# untitled.net
KiCad netlist of a schematic drawn in EAGLE
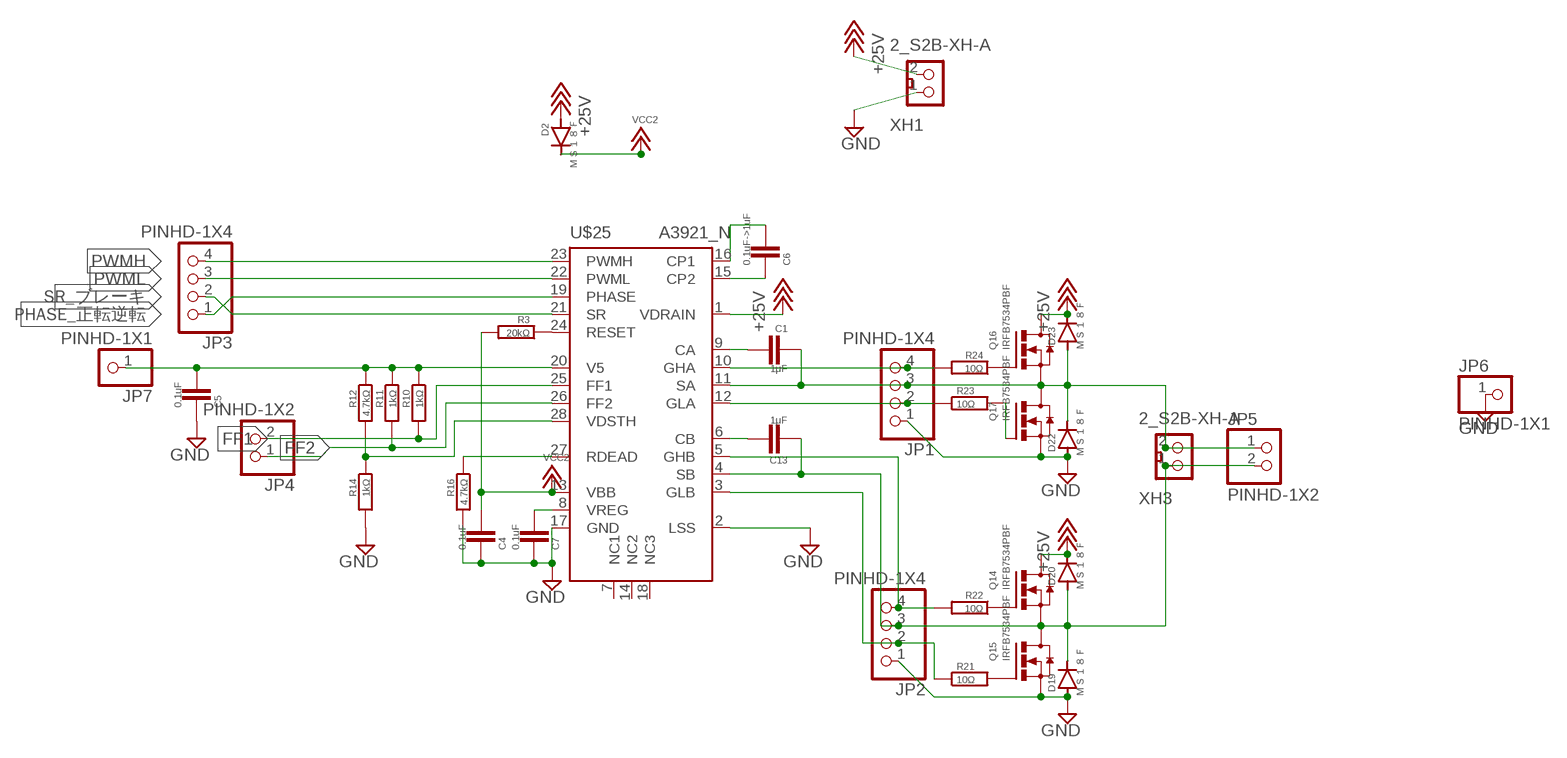
[diagram p0: schematic, sheet 1]

(export (version "E")
  (design (tool "Eeschema 10.0.6"))
  (components
    (comp (ref "C1")
      (value "1μF")
      (footprint "eagle-import:2012")
      (libsource (lib "eagle-import") (part "CAPACITOR{gt}{gt}2012"))
    )
    (comp (ref "C4")
      (value "0.1uF")
      (footprint "eagle-import:2012")
      (libsource (lib "eagle-import") (part "CAPACITOR{gt}{gt}2012"))
    )
    (comp (ref "C5")
      (value "0.1uF")
      (footprint "eagle-import:2012")
      (libsource (lib "eagle-import") (part "CAPACITOR{gt}{gt}2012"))
    )
    (comp (ref "C6")
      (value "0.1uF->1uF")
      (footprint "eagle-import:2012")
      (libsource (lib "eagle-import") (part "CAPACITOR{gt}{gt}2012"))
    )
    (comp (ref "C7")
      (value "0.1uF")
      (footprint "eagle-import:2012")
      (libsource (lib "eagle-import") (part "CAPACITOR{gt}{gt}2012"))
    )
    (comp (ref "C13")
      (value "1μF")
      (footprint "eagle-import:2012")
      (libsource (lib "eagle-import") (part "CAPACITOR{gt}{gt}2012"))
    )
    (comp (ref "D2")
      (value "ＭＳ１８Ｆ")
      (footprint "eagle-import:MS18F")
      (libsource (lib "eagle-import") (part "DIODE{gt}{gt}MS18F"))
    )
    (comp (ref "D19")
      (value "ＭＳ１８Ｆ")
      (footprint "eagle-import:MS18F")
      (libsource (lib "eagle-import") (part "DIODE{gt}{gt}MS18F"))
    )
    (comp (ref "D20")
      (value "ＭＳ１８Ｆ")
      (footprint "eagle-import:MS18F")
      (libsource (lib "eagle-import") (part "DIODE{gt}{gt}MS18F"))
    )
    (comp (ref "D22")
      (value "ＭＳ１８Ｆ")
      (footprint "eagle-import:MS18F")
      (libsource (lib "eagle-import") (part "DIODE{gt}{gt}MS18F"))
    )
    (comp (ref "D23")
      (value "ＭＳ１８Ｆ")
      (footprint "eagle-import:MS18F")
      (libsource (lib "eagle-import") (part "DIODE{gt}{gt}MS18F"))
    )
    (comp (ref "JP1")
      (value "PINHD-1X4")
      (footprint "eagle-import:1X04")
      (libsource (lib "eagle-import") (part "PINHD-1X4"))
    )
    (comp (ref "JP2")
      (value "PINHD-1X4")
      (footprint "eagle-import:1X04")
      (libsource (lib "eagle-import") (part "PINHD-1X4"))
    )
    (comp (ref "JP3")
      (value "PINHD-1X4")
      (footprint "eagle-import:1X04")
      (libsource (lib "eagle-import") (part "PINHD-1X4"))
    )
    (comp (ref "JP4")
      (value "PINHD-1X2")
      (footprint "eagle-import:1X02")
      (libsource (lib "eagle-import") (part "PINHD-1X2"))
    )
    (comp (ref "JP5")
      (value "PINHD-1X2")
      (footprint "eagle-import:1X02")
      (libsource (lib "eagle-import") (part "PINHD-1X2"))
    )
    (comp (ref "JP6")
      (value "PINHD-1X1")
      (footprint "eagle-import:1X01")
      (libsource (lib "eagle-import") (part "PINHD-1X1"))
    )
    (comp (ref "JP7")
      (value "PINHD-1X1")
      (footprint "eagle-import:1X01")
      (libsource (lib "eagle-import") (part "PINHD-1X1"))
    )
    (comp (ref "Q14")
      (value "IRFB7534PBF")
      (footprint "eagle-import:TO252")
      (libsource (lib "eagle-import") (part "MOSFET_N{gt}{gt}TO252"))
    )
    (comp (ref "Q15")
      (value "IRFB7534PBF")
      (footprint "eagle-import:TO252")
      (libsource (lib "eagle-import") (part "MOSFET_N{gt}{gt}TO252"))
    )
    (comp (ref "Q16")
      (value "IRFB7534PBF")
      (footprint "eagle-import:TO252")
      (libsource (lib "eagle-import") (part "MOSFET_N{gt}{gt}TO252"))
    )
    (comp (ref "Q17")
      (value "IRFB7534PBF")
      (footprint "eagle-import:TO252")
      (libsource (lib "eagle-import") (part "MOSFET_N{gt}{gt}TO252"))
    )
    (comp (ref "R3")
      (value "20kΩ")
      (footprint "eagle-import:2012")
      (libsource (lib "eagle-import") (part "REGISTER{gt}{gt}2012"))
    )
    (comp (ref "R10")
      (value "1kΩ")
      (footprint "eagle-import:2012")
      (libsource (lib "eagle-import") (part "REGISTER{gt}{gt}2012"))
    )
    (comp (ref "R11")
      (value "1kΩ")
      (footprint "eagle-import:2012")
      (libsource (lib "eagle-import") (part "REGISTER{gt}{gt}2012"))
    )
    (comp (ref "R12")
      (value "4.7kΩ")
      (footprint "eagle-import:2012")
      (libsource (lib "eagle-import") (part "REGISTER{gt}{gt}2012"))
    )
    (comp (ref "R14")
      (value "1kΩ")
      (footprint "eagle-import:2012")
      (libsource (lib "eagle-import") (part "REGISTER{gt}{gt}2012"))
    )
    (comp (ref "R16")
      (value "4.7kΩ")
      (footprint "eagle-import:2012")
      (libsource (lib "eagle-import") (part "REGISTER{gt}{gt}2012"))
    )
    (comp (ref "R21")
      (value "10Ω")
      (footprint "eagle-import:2012")
      (libsource (lib "eagle-import") (part "REGISTER{gt}{gt}2012"))
    )
    (comp (ref "R22")
      (value "10Ω")
      (footprint "eagle-import:2012")
      (libsource (lib "eagle-import") (part "REGISTER{gt}{gt}2012"))
    )
    (comp (ref "R23")
      (value "10Ω")
      (footprint "eagle-import:2012")
      (libsource (lib "eagle-import") (part "REGISTER{gt}{gt}2012"))
    )
    (comp (ref "R24")
      (value "10Ω")
      (footprint "eagle-import:2012")
      (libsource (lib "eagle-import") (part "REGISTER{gt}{gt}2012"))
    )
    (comp (ref "U$25")
      (value "A3921_N")
      (footprint "eagle-import:TSSOP28_N")
      (libsource (lib "eagle-import") (part "A3921_N"))
    )
    (comp (ref "XH1")
      (value "2_S2B-XH-A")
      (footprint "eagle-import:S2B-XH-A")
      (libsource (lib "eagle-import") (part "2_S2B-XH-A"))
    )
    (comp (ref "XH3")
      (value "2_S2B-XH-A")
      (footprint "eagle-import:S2B-XH-A")
      (libsource (lib "eagle-import") (part "2_S2B-XH-A"))
    )
  )
  (nets
    (net (code "1") (name "+25V") (class "Default")
      (node (ref "D2") (pin "P$1") (pinfunction "A_P$1") (pintype "passive"))
      (node (ref "D20") (pin "P$2") (pinfunction "C_P$2") (pintype "passive"))
      (node (ref "D23") (pin "P$2") (pinfunction "C_P$2") (pintype "passive"))
      (node (ref "Q14") (pin "3") (pinfunction "D_3") (pintype "passive"))
      (node (ref "Q16") (pin "3") (pinfunction "D_3") (pintype "passive"))
      (node (ref "U$25") (pin "1") (pinfunction "VDRAIN_1") (pintype "power_in"))
      (node (ref "XH1") (pin "2") (pinfunction "2_2") (pintype "passive"))
    )
    (net (code "2") (name "FF1") (class "Default")
      (node (ref "JP4") (pin "2") (pinfunction "2_2") (pintype "passive"))
      (node (ref "R10") (pin "2") (pinfunction "2_2") (pintype "passive"))
      (node (ref "U$25") (pin "25") (pinfunction "FF1_25") (pintype "output"))
    )
    (net (code "3") (name "FF2") (class "Default")
      (node (ref "JP4") (pin "1") (pinfunction "1_1") (pintype "passive"))
      (node (ref "R11") (pin "2") (pinfunction "2_2") (pintype "passive"))
      (node (ref "U$25") (pin "26") (pinfunction "FF2_26") (pintype "output"))
    )
    (net (code "4") (name "GND") (class "Default")
      (node (ref "C4") (pin "2") (pinfunction "2_2") (pintype "passive"))
      (node (ref "C5") (pin "2") (pinfunction "2_2") (pintype "passive"))
      (node (ref "C7") (pin "2") (pinfunction "2_2") (pintype "passive"))
      (node (ref "D19") (pin "P$1") (pinfunction "A_P$1") (pintype "passive"))
      (node (ref "D22") (pin "P$1") (pinfunction "A_P$1") (pintype "passive"))
      (node (ref "JP1") (pin "1") (pinfunction "1_1") (pintype "passive"))
      (node (ref "JP2") (pin "1") (pinfunction "1_1") (pintype "passive"))
      (node (ref "JP6") (pin "1") (pinfunction "1_1") (pintype "passive"))
      (node (ref "Q15") (pin "2") (pinfunction "S_2") (pintype "passive"))
      (node (ref "Q17") (pin "2") (pinfunction "S_2") (pintype "passive"))
      (node (ref "R14") (pin "2") (pinfunction "2_2") (pintype "passive"))
      (node (ref "R16") (pin "2") (pinfunction "2_2") (pintype "passive"))
      (node (ref "U$25") (pin "17") (pinfunction "GND_17") (pintype "power_in"))
      (node (ref "U$25") (pin "2") (pinfunction "LSS_2") (pintype "passive"))
      (node (ref "XH1") (pin "1") (pinfunction "1_1") (pintype "passive"))
    )
    (net (code "5") (name "Net-(D19-C)") (class "Default")
      (node (ref "C13") (pin "2") (pinfunction "2_2") (pintype "passive"))
      (node (ref "D19") (pin "P$2") (pinfunction "C_P$2") (pintype "passive"))
      (node (ref "D20") (pin "P$1") (pinfunction "A_P$1") (pintype "passive"))
      (node (ref "JP2") (pin "3") (pinfunction "3_3") (pintype "passive"))
      (node (ref "JP5") (pin "2") (pinfunction "2_2") (pintype "passive"))
      (node (ref "Q14") (pin "2") (pinfunction "S_2") (pintype "passive"))
      (node (ref "Q15") (pin "3") (pinfunction "D_3") (pintype "passive"))
      (node (ref "U$25") (pin "4") (pinfunction "SB_4") (pintype "output"))
      (node (ref "XH3") (pin "1") (pinfunction "1_1") (pintype "passive"))
    )
    (net (code "6") (name "Net-(D22-C)") (class "Default")
      (node (ref "C1") (pin "2") (pinfunction "2_2") (pintype "passive"))
      (node (ref "D22") (pin "P$2") (pinfunction "C_P$2") (pintype "passive"))
      (node (ref "D23") (pin "P$1") (pinfunction "A_P$1") (pintype "passive"))
      (node (ref "JP1") (pin "3") (pinfunction "3_3") (pintype "passive"))
      (node (ref "JP5") (pin "1") (pinfunction "1_1") (pintype "passive"))
      (node (ref "Q16") (pin "2") (pinfunction "S_2") (pintype "passive"))
      (node (ref "Q17") (pin "3") (pinfunction "D_3") (pintype "passive"))
      (node (ref "U$25") (pin "11") (pinfunction "SA_11") (pintype "output"))
      (node (ref "XH3") (pin "2") (pinfunction "2_2") (pintype "passive"))
    )
    (net (code "7") (name "Net-(Q14-G)") (class "Default")
      (node (ref "Q14") (pin "1") (pinfunction "G_1") (pintype "passive"))
      (node (ref "R22") (pin "1") (pinfunction "1_1") (pintype "passive"))
    )
    (net (code "8") (name "Net-(Q15-G)") (class "Default")
      (node (ref "Q15") (pin "1") (pinfunction "G_1") (pintype "passive"))
      (node (ref "R21") (pin "2") (pinfunction "2_2") (pintype "passive"))
    )
    (net (code "9") (name "Net-(Q16-G)") (class "Default")
      (node (ref "Q16") (pin "1") (pinfunction "G_1") (pintype "passive"))
      (node (ref "R24") (pin "1") (pinfunction "1_1") (pintype "passive"))
    )
    (net (code "10") (name "Net-(Q17-G)") (class "Default")
      (node (ref "Q17") (pin "1") (pinfunction "G_1") (pintype "passive"))
      (node (ref "R23") (pin "2") (pinfunction "2_2") (pintype "passive"))
    )
    (net (code "11") (name "Net-(U$25-CA)") (class "Default")
      (node (ref "C1") (pin "1") (pinfunction "1_1") (pintype "passive"))
      (node (ref "U$25") (pin "9") (pinfunction "CA_9") (pintype "input"))
    )
    (net (code "12") (name "Net-(U$25-CB)") (class "Default")
      (node (ref "C13") (pin "1") (pinfunction "1_1") (pintype "passive"))
      (node (ref "U$25") (pin "6") (pinfunction "CB_6") (pintype "input"))
    )
    (net (code "13") (name "Net-(U$25-CP1)") (class "Default")
      (node (ref "C6") (pin "1") (pinfunction "1_1") (pintype "passive"))
      (node (ref "U$25") (pin "16") (pinfunction "CP1_16") (pintype "passive"))
    )
    (net (code "14") (name "Net-(U$25-CP2)") (class "Default")
      (node (ref "C6") (pin "2") (pinfunction "2_2") (pintype "passive"))
      (node (ref "U$25") (pin "15") (pinfunction "CP2_15") (pintype "passive"))
    )
    (net (code "15") (name "Net-(U$25-GHA)") (class "Default")
      (node (ref "JP1") (pin "4") (pinfunction "4_4") (pintype "passive"))
      (node (ref "R24") (pin "2") (pinfunction "2_2") (pintype "passive"))
      (node (ref "U$25") (pin "10") (pinfunction "GHA_10") (pintype "output"))
    )
    (net (code "16") (name "Net-(U$25-GHB)") (class "Default")
      (node (ref "JP2") (pin "4") (pinfunction "4_4") (pintype "passive"))
      (node (ref "R22") (pin "2") (pinfunction "2_2") (pintype "passive"))
      (node (ref "U$25") (pin "5") (pinfunction "GHB_5") (pintype "output"))
    )
    (net (code "17") (name "Net-(U$25-GLA)") (class "Default")
      (node (ref "JP1") (pin "2") (pinfunction "2_2") (pintype "passive"))
      (node (ref "R23") (pin "1") (pinfunction "1_1") (pintype "passive"))
      (node (ref "U$25") (pin "12") (pinfunction "GLA_12") (pintype "output"))
    )
    (net (code "18") (name "Net-(U$25-GLB)") (class "Default")
      (node (ref "JP2") (pin "2") (pinfunction "2_2") (pintype "passive"))
      (node (ref "R21") (pin "1") (pinfunction "1_1") (pintype "passive"))
      (node (ref "U$25") (pin "3") (pinfunction "GLB_3") (pintype "output"))
    )
    (net (code "19") (name "Net-(U$25-RDEAD)") (class "Default")
      (node (ref "R16") (pin "1") (pinfunction "1_1") (pintype "passive"))
      (node (ref "U$25") (pin "27") (pinfunction "RDEAD_27") (pintype "input"))
    )
    (net (code "20") (name "Net-(U$25-RESET)") (class "Default")
      (node (ref "R3") (pin "1") (pinfunction "1_1") (pintype "passive"))
      (node (ref "U$25") (pin "24") (pinfunction "RESET_24") (pintype "input"))
    )
    (net (code "21") (name "Net-(U$25-V5)") (class "Default")
      (node (ref "C5") (pin "1") (pinfunction "1_1") (pintype "passive"))
      (node (ref "JP7") (pin "1") (pinfunction "1_1") (pintype "passive"))
      (node (ref "R10") (pin "1") (pinfunction "1_1") (pintype "passive"))
      (node (ref "R11") (pin "1") (pinfunction "1_1") (pintype "passive"))
      (node (ref "R12") (pin "1") (pinfunction "1_1") (pintype "passive"))
      (node (ref "U$25") (pin "20") (pinfunction "V5_20") (pintype "power_in"))
    )
    (net (code "22") (name "Net-(U$25-VDSTH)") (class "Default")
      (node (ref "R12") (pin "2") (pinfunction "2_2") (pintype "passive"))
      (node (ref "R14") (pin "1") (pinfunction "1_1") (pintype "passive"))
      (node (ref "U$25") (pin "28") (pinfunction "VDSTH_28") (pintype "input"))
    )
    (net (code "23") (name "Net-(U$25-VREG)") (class "Default")
      (node (ref "C7") (pin "1") (pinfunction "1_1") (pintype "passive"))
      (node (ref "U$25") (pin "8") (pinfunction "VREG_8") (pintype "power_in"))
    )
    (net (code "24") (name "PHASE_正転逆転") (class "Default")
      (node (ref "JP3") (pin "1") (pinfunction "1_1") (pintype "passive"))
      (node (ref "U$25") (pin "19") (pinfunction "PHASE_19") (pintype "input"))
    )
    (net (code "25") (name "PWMH") (class "Default")
      (node (ref "JP3") (pin "4") (pinfunction "4_4") (pintype "passive"))
      (node (ref "U$25") (pin "23") (pinfunction "PWMH_23") (pintype "input"))
    )
    (net (code "26") (name "PWML") (class "Default")
      (node (ref "JP3") (pin "3") (pinfunction "3_3") (pintype "passive"))
      (node (ref "U$25") (pin "22") (pinfunction "PWML_22") (pintype "input"))
    )
    (net (code "27") (name "SR_ブレーキ") (class "Default")
      (node (ref "JP3") (pin "2") (pinfunction "2_2") (pintype "passive"))
      (node (ref "U$25") (pin "21") (pinfunction "SR_21") (pintype "input"))
    )
    (net (code "28") (name "VCC2") (class "Default")
      (node (ref "C4") (pin "1") (pinfunction "1_1") (pintype "passive"))
      (node (ref "D2") (pin "P$2") (pinfunction "C_P$2") (pintype "passive"))
      (node (ref "R3") (pin "2") (pinfunction "2_2") (pintype "passive"))
      (node (ref "U$25") (pin "13") (pinfunction "VBB_13") (pintype "power_in"))
    )
    (net (code "29") (name "unconnected-(U$25-NC1-Pad7)") (class "Default")
      (node (ref "U$25") (pin "7") (pinfunction "NC1_7") (pintype "no_connect"))
    )
    (net (code "30") (name "unconnected-(U$25-NC2-Pad14)") (class "Default")
      (node (ref "U$25") (pin "14") (pinfunction "NC2_14") (pintype "no_connect"))
    )
    (net (code "31") (name "unconnected-(U$25-NC3-Pad18)") (class "Default")
      (node (ref "U$25") (pin "18") (pinfunction "NC3_18") (pintype "no_connect"))
    )
  )
)
